# Connect.net
KiCad netlist of a schematic drawn in Altium Designer
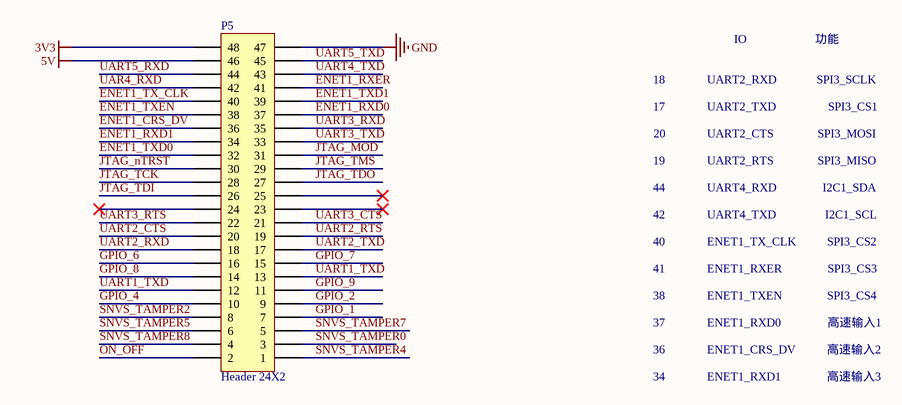
[diagram p0: Connect.SchDoc]

(export (version "E")
  (design (tool "Eeschema 10.0.6"))
  (components
    (comp (ref "P5")
      (value "Header 24X2")
      (footprint "HDR2X24")
      (description "Header, 24-Pin, Dual row")
      (fields (field (name "PUBLISHER") "Altium Limited"))
      (libsource (lib "Miscellaneous Connectors") (part "Header 24X2"))
    )
  )
  (nets
    (net (code "1") (name "/ENET1_CRS_DV") (class "Default")
      (node (ref "P5") (pin "36") (pinfunction "36_36") (pintype "passive"))
    )
    (net (code "2") (name "/ENET1_RXD0") (class "Default")
      (node (ref "P5") (pin "37") (pinfunction "37_37") (pintype "passive"))
    )
    (net (code "3") (name "/ENET1_RXD1") (class "Default")
      (node (ref "P5") (pin "34") (pinfunction "34_34") (pintype "passive"))
    )
    (net (code "4") (name "/ENET1_RXER") (class "Default")
      (node (ref "P5") (pin "41") (pinfunction "41_41") (pintype "passive"))
    )
    (net (code "5") (name "/ENET1_TXD0") (class "Default")
      (node (ref "P5") (pin "32") (pinfunction "32_32") (pintype "passive"))
    )
    (net (code "6") (name "/ENET1_TXD1") (class "Default")
      (node (ref "P5") (pin "39") (pinfunction "39_39") (pintype "passive"))
    )
    (net (code "7") (name "/ENET1_TXEN") (class "Default")
      (node (ref "P5") (pin "38") (pinfunction "38_38") (pintype "passive"))
    )
    (net (code "8") (name "/ENET1_TX_CLK") (class "Default")
      (node (ref "P5") (pin "40") (pinfunction "40_40") (pintype "passive"))
    )
    (net (code "9") (name "/GPIO_1") (class "Default")
      (node (ref "P5") (pin "7") (pinfunction "7_7") (pintype "passive"))
    )
    (net (code "10") (name "/GPIO_2") (class "Default")
      (node (ref "P5") (pin "9") (pinfunction "9_9") (pintype "passive"))
    )
    (net (code "11") (name "/GPIO_4") (class "Default")
      (node (ref "P5") (pin "10") (pinfunction "10_10") (pintype "passive"))
    )
    (net (code "12") (name "/GPIO_6") (class "Default")
      (node (ref "P5") (pin "16") (pinfunction "16_16") (pintype "passive"))
    )
    (net (code "13") (name "/GPIO_7") (class "Default")
      (node (ref "P5") (pin "15") (pinfunction "15_15") (pintype "passive"))
    )
    (net (code "14") (name "/GPIO_8") (class "Default")
      (node (ref "P5") (pin "14") (pinfunction "14_14") (pintype "passive"))
    )
    (net (code "15") (name "/GPIO_9") (class "Default")
      (node (ref "P5") (pin "11") (pinfunction "11_11") (pintype "passive"))
    )
    (net (code "16") (name "/JTAG_MOD") (class "Default")
      (node (ref "P5") (pin "31") (pinfunction "31_31") (pintype "passive"))
    )
    (net (code "17") (name "/JTAG_TCK") (class "Default")
      (node (ref "P5") (pin "28") (pinfunction "28_28") (pintype "passive"))
    )
    (net (code "18") (name "/JTAG_TDI") (class "Default")
      (node (ref "P5") (pin "26") (pinfunction "26_26") (pintype "passive"))
    )
    (net (code "19") (name "/JTAG_TDO") (class "Default")
      (node (ref "P5") (pin "27") (pinfunction "27_27") (pintype "passive"))
    )
    (net (code "20") (name "/JTAG_TMS") (class "Default")
      (node (ref "P5") (pin "29") (pinfunction "29_29") (pintype "passive"))
    )
    (net (code "21") (name "/JTAG_nTRST") (class "Default")
      (node (ref "P5") (pin "30") (pinfunction "30_30") (pintype "passive"))
    )
    (net (code "22") (name "/ON_OFF") (class "Default")
      (node (ref "P5") (pin "2") (pinfunction "2_2") (pintype "passive"))
    )
    (net (code "23") (name "/SNVS_TAMPER0") (class "Default")
      (node (ref "P5") (pin "3") (pinfunction "3_3") (pintype "passive"))
    )
    (net (code "24") (name "/SNVS_TAMPER2") (class "Default")
      (node (ref "P5") (pin "8") (pinfunction "8_8") (pintype "passive"))
    )
    (net (code "25") (name "/SNVS_TAMPER4") (class "Default")
      (node (ref "P5") (pin "1") (pinfunction "1_1") (pintype "passive"))
    )
    (net (code "26") (name "/SNVS_TAMPER5") (class "Default")
      (node (ref "P5") (pin "6") (pinfunction "6_6") (pintype "passive"))
    )
    (net (code "27") (name "/SNVS_TAMPER7") (class "Default")
      (node (ref "P5") (pin "5") (pinfunction "5_5") (pintype "passive"))
    )
    (net (code "28") (name "/SNVS_TAMPER8") (class "Default")
      (node (ref "P5") (pin "4") (pinfunction "4_4") (pintype "passive"))
    )
    (net (code "29") (name "/UAR4_RXD") (class "Default")
      (node (ref "P5") (pin "42") (pinfunction "42_42") (pintype "passive"))
    )
    (net (code "30") (name "/UART1_TXD") (class "Default")
      (node (ref "P5") (pin "12") (pinfunction "12_12") (pintype "passive"))
      (node (ref "P5") (pin "13") (pinfunction "13_13") (pintype "passive"))
    )
    (net (code "31") (name "/UART2_CTS") (class "Default")
      (node (ref "P5") (pin "20") (pinfunction "20_20") (pintype "passive"))
    )
    (net (code "32") (name "/UART2_RTS") (class "Default")
      (node (ref "P5") (pin "19") (pinfunction "19_19") (pintype "passive"))
    )
    (net (code "33") (name "/UART2_RXD") (class "Default")
      (node (ref "P5") (pin "18") (pinfunction "18_18") (pintype "passive"))
    )
    (net (code "34") (name "/UART2_TXD") (class "Default")
      (node (ref "P5") (pin "17") (pinfunction "17_17") (pintype "passive"))
    )
    (net (code "35") (name "/UART3_CTS") (class "Default")
      (node (ref "P5") (pin "21") (pinfunction "21_21") (pintype "passive"))
    )
    (net (code "36") (name "/UART3_RTS") (class "Default")
      (node (ref "P5") (pin "22") (pinfunction "22_22") (pintype "passive"))
    )
    (net (code "37") (name "/UART3_RXD") (class "Default")
      (node (ref "P5") (pin "35") (pinfunction "35_35") (pintype "passive"))
    )
    (net (code "38") (name "/UART3_TXD") (class "Default")
      (node (ref "P5") (pin "33") (pinfunction "33_33") (pintype "passive"))
    )
    (net (code "39") (name "/UART4_TXD") (class "Default")
      (node (ref "P5") (pin "43") (pinfunction "43_43") (pintype "passive"))
    )
    (net (code "40") (name "/UART5_RXD") (class "Default")
      (node (ref "P5") (pin "44") (pinfunction "44_44") (pintype "passive"))
    )
    (net (code "41") (name "/UART5_TXD") (class "Default")
      (node (ref "P5") (pin "45") (pinfunction "45_45") (pintype "passive"))
    )
    (net (code "42") (name "3V3") (class "Default")
      (node (ref "P5") (pin "48") (pinfunction "48_48") (pintype "passive"))
    )
    (net (code "43") (name "5V") (class "Default")
      (node (ref "P5") (pin "46") (pinfunction "46_46") (pintype "passive"))
    )
    (net (code "44") (name "GND") (class "Default")
      (node (ref "P5") (pin "47") (pinfunction "47_47") (pintype "passive"))
    )
    (net (code "45") (name "unconnected-(P5-Pad23)") (class "Default")
      (node (ref "P5") (pin "23") (pinfunction "23_23") (pintype "passive+no_connect"))
    )
    (net (code "46") (name "unconnected-(P5-Pad24)") (class "Default")
      (node (ref "P5") (pin "24") (pinfunction "24_24") (pintype "passive+no_connect"))
    )
    (net (code "47") (name "unconnected-(P5-Pad25)") (class "Default")
      (node (ref "P5") (pin "25") (pinfunction "25_25") (pintype "passive+no_connect"))
    )
  )
)
